# 05-STM32.net
KiCad netlist of a schematic drawn in Altium Designer
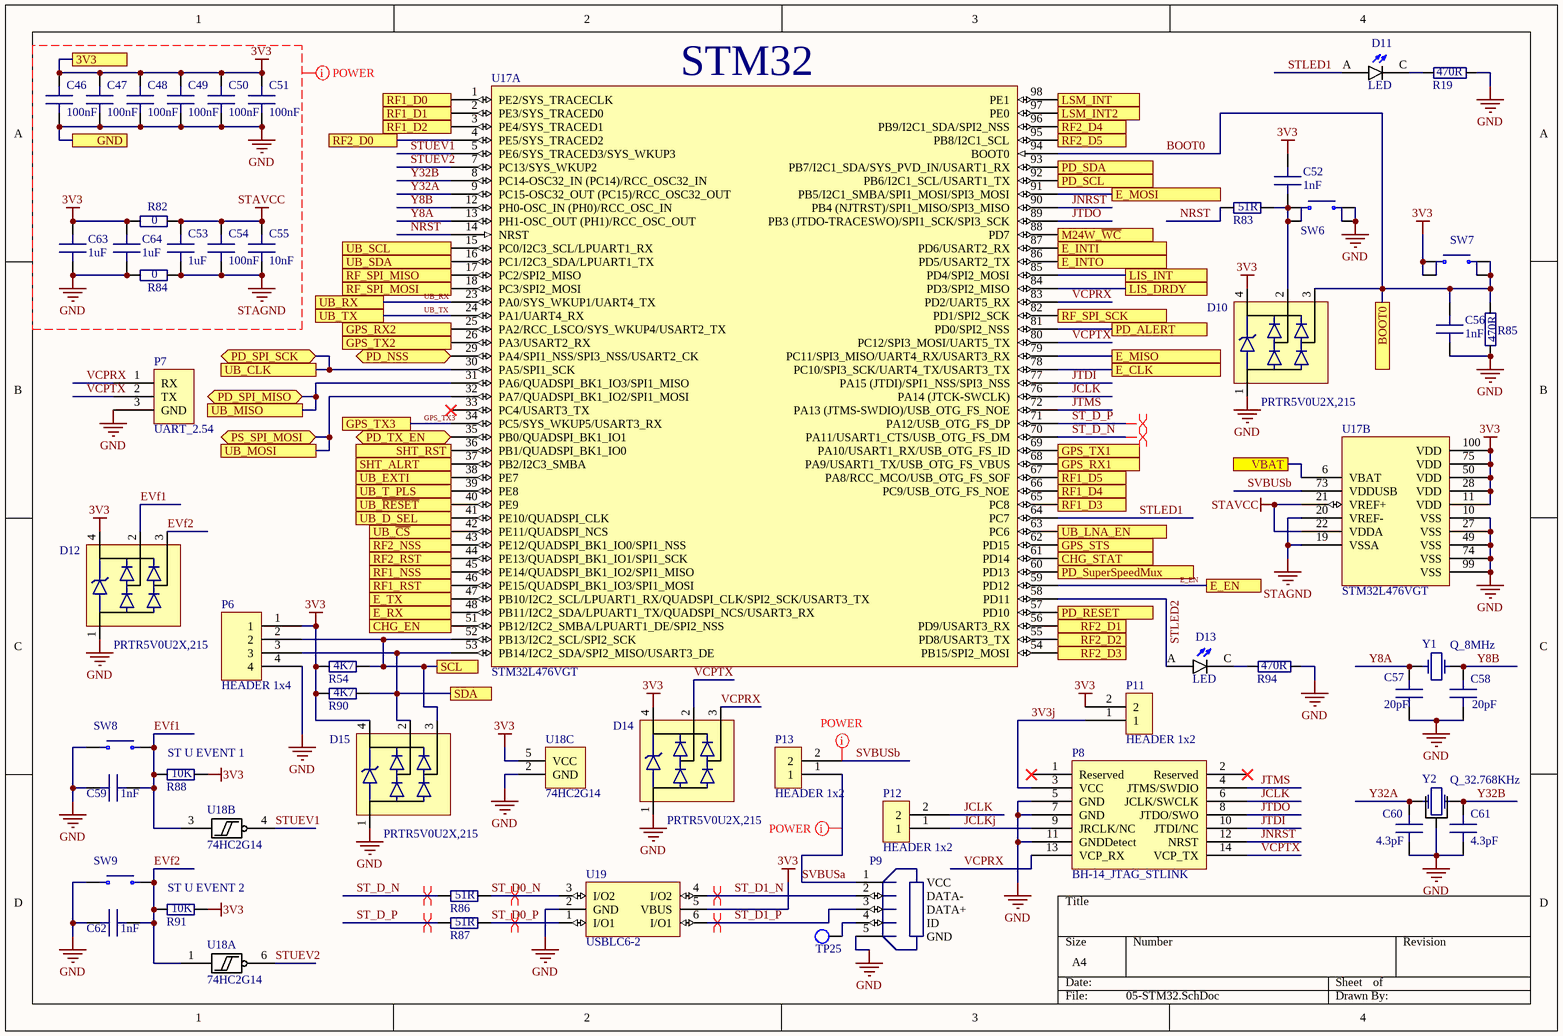
[diagram p0: 05-STM32.SchDoc]

(export (version "E")
  (design (tool "Eeschema 10.0.6"))
  (components
    (comp (ref "C46")
      (value "100nF")
      (footprint "C0603")
      (description "Ceramic capacitor")
      (fields (field (name "VOLTAGE") "16V"))
      (libsource (lib "A.Shelestov_Capacitors") (part "C0603_100nF_16V"))
    )
    (comp (ref "C47")
      (value "100nF")
      (footprint "C0603_NOSILK")
      (description "Ceramic capacitor")
      (fields (field (name "VOLTAGE") "16V"))
      (libsource (lib "A.Shelestov_Capacitors") (part "C0603_100nF_16V"))
    )
    (comp (ref "C48")
      (value "100nF")
      (footprint "C0603")
      (description "Ceramic capacitor")
      (fields (field (name "VOLTAGE") "16V"))
      (libsource (lib "A.Shelestov_Capacitors") (part "C0603_100nF_16V"))
    )
    (comp (ref "C49")
      (value "100nF")
      (footprint "C0603")
      (description "Ceramic capacitor")
      (fields (field (name "VOLTAGE") "16V"))
      (libsource (lib "A.Shelestov_Capacitors") (part "C0603_100nF_16V"))
    )
    (comp (ref "C50")
      (value "100nF")
      (footprint "C0603")
      (description "Ceramic capacitor")
      (fields (field (name "VOLTAGE") "16V"))
      (libsource (lib "A.Shelestov_Capacitors") (part "C0603_100nF_16V"))
    )
    (comp (ref "C51")
      (value "100nF")
      (footprint "C0603")
      (description "Ceramic capacitor")
      (fields (field (name "VOLTAGE") "16V"))
      (libsource (lib "A.Shelestov_Capacitors") (part "C0603_100nF_16V"))
    )
    (comp (ref "C52")
      (value "1nF")
      (footprint "C0603")
      (description "Ceramic capacitor")
      (fields (field (name "VOLTAGE") "25V"))
      (libsource (lib "A.Shelestov_Capacitors") (part "C0603_1nF_25V"))
    )
    (comp (ref "C53")
      (value "1uF")
      (footprint "C0805")
      (description "Ceramic capacitor")
      (fields (field (name "VOLTAGE") "25V"))
      (libsource (lib "A.Shelestov_Capacitors") (part "C0805_1uF_25V"))
    )
    (comp (ref "C54")
      (value "100nF")
      (footprint "C0603")
      (description "Ceramic capacitor")
      (fields (field (name "VOLTAGE") "16V"))
      (libsource (lib "A.Shelestov_Capacitors") (part "C0603_100nF_16V"))
    )
    (comp (ref "C55")
      (value "10nF")
      (footprint "C0603")
      (description "Ceramic capacitor")
      (fields (field (name "VOLTAGE") "16V"))
      (libsource (lib "A.Shelestov_Capacitors") (part "C0603_10nF_16V"))
    )
    (comp (ref "C56")
      (value "1nF")
      (footprint "C0603")
      (description "Ceramic capacitor")
      (fields (field (name "VOLTAGE") "25V"))
      (libsource (lib "A.Shelestov_Capacitors") (part "C0603_1nF_25V"))
    )
    (comp (ref "C57")
      (value "20pF")
      (footprint "C0603")
      (description "Ceramic capacitor")
      (fields (field (name "VOLTAGE") "25V"))
      (libsource (lib "A.Shelestov_Capacitors") (part "C0603_20pF_50V"))
    )
    (comp (ref "C58")
      (value "20pF")
      (footprint "C0603")
      (description "Ceramic capacitor")
      (fields (field (name "VOLTAGE") "25V"))
      (libsource (lib "A.Shelestov_Capacitors") (part "C0603_20pF_50V"))
    )
    (comp (ref "C59")
      (value "1nF")
      (footprint "C0603")
      (description "Ceramic capacitor")
      (fields (field (name "VOLTAGE") "25V"))
      (libsource (lib "A.Shelestov_Capacitors") (part "C0603_1nF_25V"))
    )
    (comp (ref "C60")
      (value "4.3pF")
      (footprint "C0603")
      (description "Ceramic capacitor")
      (fields (field (name "VOLTAGE") "25V"))
      (libsource (lib "A.Shelestov_Capacitors") (part "C0603_4.3pF_50V"))
    )
    (comp (ref "C61")
      (value "4.3pF")
      (footprint "C0603")
      (description "Ceramic capacitor")
      (fields (field (name "VOLTAGE") "25V"))
      (libsource (lib "A.Shelestov_Capacitors") (part "C0603_4.3pF_50V"))
    )
    (comp (ref "C62")
      (value "1nF")
      (footprint "C0603")
      (description "Ceramic capacitor")
      (fields (field (name "VOLTAGE") "25V"))
      (libsource (lib "A.Shelestov_Capacitors") (part "C0603_1nF_25V"))
    )
    (comp (ref "C63")
      (value "1uF")
      (footprint "C0805")
      (description "Ceramic capacitor")
      (fields (field (name "VOLTAGE") "25V"))
      (libsource (lib "A.Shelestov_Capacitors") (part "C0805_1uF_25V"))
    )
    (comp (ref "C64")
      (value "1uF")
      (footprint "C0805")
      (description "Ceramic capacitor")
      (fields (field (name "VOLTAGE") "25V"))
      (libsource (lib "A.Shelestov_Capacitors") (part "C0805_1uF_25V"))
    )
    (comp (ref "D10")
      (value "PRTR5V0U2X,215")
      (footprint "SOT143B")
      (description "PRTR5V0U2X - Ultra low capacitance double rail-to-rail ESD protection diode")
      (fields (field (name "MF") "Nexperia USA"))
      (libsource (lib "ComponentsLib") (part "PRTR5V0U2X,215"))
    )
    (comp (ref "D11")
      (value "LED")
      (footprint "LED_0604")
      (description "Led General")
      (fields (field (name "MF") "Dialight") (field (name "MP") "598-8140-107F"))
      (libsource (lib "ComponentsLib") (part "LED"))
    )
    (comp (ref "D12")
      (value "PRTR5V0U2X,215")
      (footprint "SOT143B")
      (description "PRTR5V0U2X - Ultra low capacitance double rail-to-rail ESD protection diode")
      (fields (field (name "MF") "Nexperia USA"))
      (libsource (lib "ComponentsLib") (part "PRTR5V0U2X,215"))
    )
    (comp (ref "D13")
      (value "LED")
      (footprint "LED_0604")
      (description "Led General")
      (fields (field (name "MF") "Dialight") (field (name "MP") "598-8140-107F"))
      (libsource (lib "ComponentsLib") (part "LED"))
    )
    (comp (ref "D14")
      (value "PRTR5V0U2X,215")
      (footprint "SOT143B")
      (description "PRTR5V0U2X - Ultra low capacitance double rail-to-rail ESD protection diode")
      (fields (field (name "MF") "Nexperia USA"))
      (libsource (lib "ComponentsLib") (part "PRTR5V0U2X,215"))
    )
    (comp (ref "D15")
      (value "PRTR5V0U2X,215")
      (footprint "SOT143B")
      (description "PRTR5V0U2X - Ultra low capacitance double rail-to-rail ESD protection diode")
      (fields (field (name "MF") "Nexperia USA"))
      (libsource (lib "ComponentsLib") (part "PRTR5V0U2X,215"))
    )
    (comp (ref "P6")
      (value "HEADER 1x4")
      (footprint "HEADER 1x4 2.54")
      (libsource (lib "ComponentsLib") (part "HEADER 1x4"))
    )
    (comp (ref "P7")
      (value "UART_2.54")
      (footprint "UART_2.54")
      (libsource (lib "ComponentsLib") (part "UART_2.54"))
    )
    (comp (ref "P8")
      (value "BH-14_JTAG_STLINK")
      (footprint "BH-14-1.27")
      (description "1,27 mm 2x7 Header")
      (libsource (lib "ComponentsLib") (part "BH-14_JTAG_STLINK"))
    )
    (comp (ref "P9")
      (value "440247-2")
      (footprint "CON-UUSB-F-2")
      (description "Mini/Micro USB B Type RCPT")
      (fields (field (name "MF") "TE Connectivity"))
      (libsource (lib "ComponentsLib") (part "CON-USB-Micro/Mini"))
    )
    (comp (ref "P11")
      (value "HEADER 1x2")
      (footprint "HEADER 1x2 2.54")
      (libsource (lib "ComponentsLib") (part "HEADER 1x2"))
    )
    (comp (ref "P12")
      (value "HEADER 1x2")
      (footprint "HEADER 1x2 2.54")
      (libsource (lib "") (part "HEADER 1x2_1"))
    )
    (comp (ref "P13")
      (value "HEADER 1x2")
      (footprint "HEADER 1x2 2.54")
      (libsource (lib "") (part "HEADER 1x2_1"))
    )
    (comp (ref "R19")
      (value "~")
      (footprint "R0603")
      (description "Resistor General")
      (fields (field (name "TOLERANCE") "5%") (field (name "RESISTANCE") "470R"))
      (libsource (lib "A.Shelestov_Resistors") (part "R0603_470R"))
    )
    (comp (ref "R54")
      (value "~")
      (footprint "R0603")
      (description "Resistor General")
      (fields (field (name "TOLERANCE") "5%") (field (name "RESISTANCE") "4K7"))
      (libsource (lib "A.Shelestov_Resistors") (part "R0603_4K7"))
    )
    (comp (ref "R82")
      (value "~")
      (footprint "R0603")
      (description "Resistor General")
      (fields (field (name "RESISTANCE") "0"))
      (libsource (lib "A.Shelestov_Resistors") (part "R0603_0R"))
    )
    (comp (ref "R83")
      (value "~")
      (footprint "R0402")
      (description "Resistor General")
      (fields (field (name "RESISTANCE") "51R"))
      (libsource (lib "A.Shelestov_Resistors") (part "R0402_51R"))
    )
    (comp (ref "R84")
      (value "~")
      (footprint "R0603")
      (description "Resistor General")
      (fields (field (name "RESISTANCE") "0"))
      (libsource (lib "A.Shelestov_Resistors") (part "R0603_0R"))
    )
    (comp (ref "R85")
      (value "~")
      (footprint "R0603")
      (description "Resistor General")
      (fields (field (name "TOLERANCE") "5%") (field (name "RESISTANCE") "470R"))
      (libsource (lib "A.Shelestov_Resistors") (part "R0603_470R"))
    )
    (comp (ref "R86")
      (value "~")
      (footprint "R0402")
      (description "Resistor General")
      (fields (field (name "RESISTANCE") "51R"))
      (libsource (lib "A.Shelestov_Resistors") (part "R0402_51R"))
    )
    (comp (ref "R87")
      (value "~")
      (footprint "R0402")
      (description "Resistor General")
      (fields (field (name "RESISTANCE") "51R"))
      (libsource (lib "A.Shelestov_Resistors") (part "R0402_51R"))
    )
    (comp (ref "R88")
      (value "~")
      (footprint "R0603")
      (description "Resistor General")
      (fields (field (name "TOLERANCE") "5%") (field (name "RESISTANCE") "10K"))
      (libsource (lib "A.Shelestov_Resistors") (part "R0603_10K"))
    )
    (comp (ref "R90")
      (value "~")
      (footprint "R0603")
      (description "Resistor General")
      (fields (field (name "TOLERANCE") "5%") (field (name "RESISTANCE") "4K7"))
      (libsource (lib "A.Shelestov_Resistors") (part "R0603_4K7"))
    )
    (comp (ref "R91")
      (value "~")
      (footprint "R0603")
      (description "Resistor General")
      (fields (field (name "TOLERANCE") "5%") (field (name "RESISTANCE") "10K"))
      (libsource (lib "A.Shelestov_Resistors") (part "R0603_10K"))
    )
    (comp (ref "R94")
      (value "~")
      (footprint "R0603")
      (description "Resistor General")
      (fields (field (name "TOLERANCE") "5%") (field (name "RESISTANCE") "470R"))
      (libsource (lib "A.Shelestov_Resistors") (part "R0603_470R"))
    )
    (comp (ref "SW6")
      (value "SWITCH_GEN_4P")
      (footprint "SW_4x4x1.5")
      (description "SWITCH DIP 4.3 mm")
      (libsource (lib "ComponentsLib") (part "SWITCH_GEN_4P"))
    )
    (comp (ref "SW7")
      (value "SWITCH_GEN_4P")
      (footprint "SW_4x4x1.5")
      (description "SWITCH DIP 4.3 mm")
      (libsource (lib "ComponentsLib") (part "SWITCH_GEN_4P"))
    )
    (comp (ref "SW8")
      (value "SWITCH_GEN_2P")
      (footprint "SW_TACTM-35N-F")
      (description "SWITCH DIP 4.3 mm")
      (libsource (lib "ComponentsLib") (part "SWITCH_GEN_2P"))
    )
    (comp (ref "SW9")
      (value "SWITCH_GEN_2P")
      (footprint "SW_TACTM-35N-F")
      (description "SWITCH DIP 4.3 mm")
      (libsource (lib "ComponentsLib") (part "SWITCH_GEN_2P"))
    )
    (comp (ref "TP25")
      (value "TEST_POINT")
      (footprint "TP_1mm")
      (libsource (lib "ComponentsLib") (part "TEST_POINT"))
    )
    (comp (ref "U17")
      (value "STM32L476VGT")
      (footprint "LQFP100_0.5")
      (description "Ultra-low-power Cortex-M4 32-bit MCU+FPU, 100DMIPS, up to 1MB Flash, 128 KB SRAM, USB OTG FS, LCD")
      (libsource (lib "ComponentsLib") (part "STM32L476VGT"))
    )
    (comp (ref "U18")
      (value "74HC2G14")
      (footprint "SOT363/SOT65P210X110-6N")
      (description "Dual inverting Schmitt trigger")
      (libsource (lib "ComponentsLib") (part "74HC2G14"))
    )
    (comp (ref "U19")
      (value "USBLC6-2")
      (footprint "SOT-666")
      (description "Very low capacitance ESD protection")
      (libsource (lib "ComponentsLib") (part "USBLC6-2"))
    )
    (comp (ref "Y1")
      (value "Q_8MHz")
      (footprint "QSMD12.3x4.5x4.2")
      (description "Quartz resonator 8MHz")
      (libsource (lib "ComponentsLib") (part "Q_8MHz"))
    )
    (comp (ref "Y2")
      (value "Q_32.768KHz")
      (footprint "HC_3.0x8.0")
      (description "Quartz resonator 32.768KHz")
      (libsource (lib "ComponentsLib") (part "Q_32.768KHz"))
    )
  )
  (nets
    (net (code "1") (name "/3V3j") (class "Default")
      (node (ref "P11") (pin "1") (pinfunction "1_1") (pintype "passive"))
      (node (ref "P8") (pin "3") (pinfunction "VCC_3") (pintype "passive"))
    )
    (net (code "2") (name "/BOOT0") (class "Default")
      (node (ref "C56") (pin "1") (pinfunction "1_1") (pintype "passive"))
      (node (ref "D10") (pin "3") (pinfunction "P$3_3") (pintype "passive"))
      (node (ref "R85") (pin "2") (pinfunction "2_2") (pintype "passive"))
      (node (ref "SW7") (pin "1") (pinfunction "1_1") (pintype "passive"))
      (node (ref "SW7") (pin "3") (pinfunction "3_3") (pintype "passive"))
      (node (ref "U17") (pin "94") (pinfunction "BOOT0_94") (pintype "input"))
    )
    (net (code "3") (name "/CHG_EN") (class "Default")
      (node (ref "U17") (pin "51") (pinfunction "PB12/I2C2_SMBA/LPUART1_DE/SPI2_NSS_51") (pintype "bidirectional"))
    )
    (net (code "4") (name "/CHG_STAT") (class "Default")
      (node (ref "U17") (pin "61") (pinfunction "PD14_61") (pintype "bidirectional"))
    )
    (net (code "5") (name "/EVf1") (class "Default")
      (node (ref "C59") (pin "1") (pinfunction "1_1") (pintype "passive"))
      (node (ref "D12") (pin "2") (pinfunction "P$2_2") (pintype "passive"))
      (node (ref "R88") (pin "1") (pinfunction "1_1") (pintype "passive"))
      (node (ref "SW8") (pin "2") (pinfunction "2_2") (pintype "passive"))
      (node (ref "U18") (pin "3") (pinfunction "2A_3") (pintype "passive"))
    )
    (net (code "6") (name "/EVf2") (class "Default")
      (node (ref "C62") (pin "1") (pinfunction "1_1") (pintype "passive"))
      (node (ref "D12") (pin "3") (pinfunction "P$3_3") (pintype "passive"))
      (node (ref "R91") (pin "1") (pinfunction "1_1") (pintype "passive"))
      (node (ref "SW9") (pin "2") (pinfunction "2_2") (pintype "passive"))
      (node (ref "U18") (pin "1") (pinfunction "1A_1") (pintype "passive"))
    )
    (net (code "7") (name "/E_CLK") (class "Default")
      (node (ref "U17") (pin "78") (pinfunction "PC10/SPI3_SCK/UART4_TX/USART3_TX_78") (pintype "bidirectional"))
    )
    (net (code "8") (name "/E_EN") (class "Default")
      (node (ref "U17") (pin "59") (pinfunction "PD12_59") (pintype "bidirectional"))
    )
    (net (code "9") (name "/E_INTI") (class "Default")
      (node (ref "U17") (pin "87") (pinfunction "PD6/USART2_RX_87") (pintype "bidirectional"))
    )
    (net (code "10") (name "/E_INTO") (class "Default")
      (node (ref "U17") (pin "86") (pinfunction "PD5/USART2_TX_86") (pintype "bidirectional"))
    )
    (net (code "11") (name "/E_MISO") (class "Default")
      (node (ref "U17") (pin "79") (pinfunction "PC11/SPI3_MISO/UART4_RX/USART3_RX_79") (pintype "bidirectional"))
    )
    (net (code "12") (name "/E_MOSI") (class "Default")
      (node (ref "U17") (pin "91") (pinfunction "PB5/I2C1_SMBA/SPI1_MOSI/SPI3_MOSI_91") (pintype "bidirectional"))
    )
    (net (code "13") (name "/E_RX") (class "Default")
      (node (ref "U17") (pin "48") (pinfunction "PB11/I2C2_SDA/LPUART1_TX/QUADSPI_NCS/USART3_RX_48") (pintype "bidirectional"))
    )
    (net (code "14") (name "/E_TX") (class "Default")
      (node (ref "U17") (pin "47") (pinfunction "PB10/I2C2_SCL/LPUART1_RX/QUADSPI_CLK/SPI2_SCK/USART3_TX_47") (pintype "bidirectional"))
    )
    (net (code "15") (name "/GPS_RX1") (class "Default")
      (node (ref "U17") (pin "68") (pinfunction "PA9/USART1_TX/USB_OTG_FS_VBUS_68") (pintype "bidirectional"))
    )
    (net (code "16") (name "/GPS_RX2") (class "Default")
      (node (ref "U17") (pin "25") (pinfunction "PA2/RCC_LSCO/SYS_WKUP4/USART2_TX_25") (pintype "bidirectional"))
    )
    (net (code "17") (name "/GPS_STS") (class "Default")
      (node (ref "U17") (pin "62") (pinfunction "PD15_62") (pintype "bidirectional"))
    )
    (net (code "18") (name "/GPS_TX1") (class "Default")
      (node (ref "U17") (pin "69") (pinfunction "PA10/USART1_RX/USB_OTG_FS_ID_69") (pintype "bidirectional"))
    )
    (net (code "19") (name "/GPS_TX2") (class "Default")
      (node (ref "U17") (pin "26") (pinfunction "PA3/USART2_RX_26") (pintype "bidirectional"))
    )
    (net (code "20") (name "/GPS_TX3") (class "Default")
      (node (ref "U17") (pin "34") (pinfunction "PC5/SYS_WKUP5/USART3_RX_34") (pintype "bidirectional"))
    )
    (net (code "21") (name "/JCLK") (class "Default")
      (node (ref "P12") (pin "2") (pinfunction "2_2") (pintype "passive"))
      (node (ref "P8") (pin "6") (pinfunction "JCLK/SWCLK_6") (pintype "passive"))
      (node (ref "U17") (pin "76") (pinfunction "PA14_(JTCK-SWCLK)_76") (pintype "bidirectional"))
    )
    (net (code "22") (name "/JCLKj") (class "Default")
      (node (ref "P12") (pin "1") (pinfunction "1_1") (pintype "passive"))
      (node (ref "P8") (pin "9") (pinfunction "JRCLK/NC_9") (pintype "passive"))
    )
    (net (code "23") (name "/JNRST") (class "Default")
      (node (ref "P8") (pin "12") (pinfunction "NRST_12") (pintype "passive"))
      (node (ref "U17") (pin "90") (pinfunction "PB4_(NJTRST)/SPI1_MISO/SPI3_MISO_90") (pintype "bidirectional"))
    )
    (net (code "24") (name "/JTDI") (class "Default")
      (node (ref "P8") (pin "10") (pinfunction "JTDI/NC_10") (pintype "passive"))
      (node (ref "U17") (pin "77") (pinfunction "PA15_(JTDI)/SPI1_NSS/SPI3_NSS_77") (pintype "bidirectional"))
    )
    (net (code "25") (name "/JTDO") (class "Default")
      (node (ref "P8") (pin "8") (pinfunction "JTDO/SWO_8") (pintype "passive"))
      (node (ref "U17") (pin "89") (pinfunction "PB3_(JTDO-TRACESWO)/SPI1_SCK/SPI3_SCK_89") (pintype "bidirectional"))
    )
    (net (code "26") (name "/JTMS") (class "Default")
      (node (ref "P8") (pin "4") (pinfunction "JTMS/SWDIO_4") (pintype "passive"))
      (node (ref "U17") (pin "72") (pinfunction "PA13_(JTMS-SWDIO)/USB_OTG_FS_NOE_72") (pintype "bidirectional"))
    )
    (net (code "27") (name "/LIS_DRDY") (class "Default")
      (node (ref "U17") (pin "84") (pinfunction "PD3/SPI2_MISO_84") (pintype "bidirectional"))
    )
    (net (code "28") (name "/LIS_INT") (class "Default")
      (node (ref "U17") (pin "85") (pinfunction "PD4/SPI2_MOSI_85") (pintype "bidirectional"))
    )
    (net (code "29") (name "/LSM_INT") (class "Default")
      (node (ref "U17") (pin "98") (pinfunction "PE1_98") (pintype "bidirectional"))
    )
    (net (code "30") (name "/LSM_INT2") (class "Default")
      (node (ref "U17") (pin "97") (pinfunction "PE0_97") (pintype "bidirectional"))
    )
    (net (code "31") (name "/M24W_~{WC}") (class "Default")
      (node (ref "U17") (pin "88") (pinfunction "PD7_88") (pintype "bidirectional"))
    )
    (net (code "32") (name "/NRST") (class "Default")
      (node (ref "R83") (pin "1") (pinfunction "1_1") (pintype "passive"))
      (node (ref "U17") (pin "14") (pinfunction "NRST_14") (pintype "input"))
    )
    (net (code "33") (name "/PD_ALERT") (class "Default")
      (node (ref "U17") (pin "81") (pinfunction "PD0/SPI2_NSS_81") (pintype "bidirectional"))
    )
    (net (code "34") (name "/PD_NSS") (class "Default")
      (node (ref "U17") (pin "29") (pinfunction "PA4/SPI1_NSS/SPI3_NSS/USART2_CK_29") (pintype "bidirectional"))
    )
    (net (code "35") (name "/PD_RESET") (class "Default")
      (node (ref "U17") (pin "57") (pinfunction "PD10_57") (pintype "bidirectional"))
    )
    (net (code "36") (name "/PD_SCL") (class "Default")
      (node (ref "U17") (pin "92") (pinfunction "PB6/I2C1_SCL/USART1_TX_92") (pintype "bidirectional"))
    )
    (net (code "37") (name "/PD_SDA") (class "Default")
      (node (ref "U17") (pin "93") (pinfunction "PB7/I2C1_SDA/SYS_PVD_IN/USART1_RX_93") (pintype "bidirectional"))
    )
    (net (code "38") (name "/PD_SPI_MISO") (class "Default")
      (node (ref "U17") (pin "31") (pinfunction "PA6/QUADSPI_BK1_IO3/SPI1_MISO_31") (pintype "bidirectional"))
    )
    (net (code "39") (name "/PD_SPI_SCK") (class "Default")
      (node (ref "U17") (pin "30") (pinfunction "PA5/SPI1_SCK_30") (pintype "bidirectional"))
    )
    (net (code "40") (name "/PD_SuperSpeedMux") (class "Default")
      (node (ref "U17") (pin "60") (pinfunction "PD13_60") (pintype "bidirectional"))
    )
    (net (code "41") (name "/PD_TX_EN") (class "Default")
      (node (ref "U17") (pin "35") (pinfunction "PB0/QUADSPI_BK1_IO1_35") (pintype "bidirectional"))
    )
    (net (code "42") (name "/PS_SPI_MOSI") (class "Default")
      (node (ref "U17") (pin "32") (pinfunction "PA7/QUADSPI_BK1_IO2/SPI1_MOSI_32") (pintype "bidirectional"))
    )
    (net (code "43") (name "/RF1_D0") (class "Default")
      (node (ref "U17") (pin "1") (pinfunction "PE2/SYS_TRACECLK_1") (pintype "bidirectional"))
    )
    (net (code "44") (name "/RF1_D1") (class "Default")
      (node (ref "U17") (pin "2") (pinfunction "PE3/SYS_TRACED0_2") (pintype "bidirectional"))
    )
    (net (code "45") (name "/RF1_D2") (class "Default")
      (node (ref "U17") (pin "3") (pinfunction "PE4/SYS_TRACED1_3") (pintype "bidirectional"))
    )
    (net (code "46") (name "/RF1_D3") (class "Default")
      (node (ref "U17") (pin "65") (pinfunction "PC8_65") (pintype "bidirectional"))
    )
    (net (code "47") (name "/RF1_D4") (class "Default")
      (node (ref "U17") (pin "66") (pinfunction "PC9/USB_OTG_FS_NOE_66") (pintype "bidirectional"))
    )
    (net (code "48") (name "/RF1_D5") (class "Default")
      (node (ref "U17") (pin "67") (pinfunction "PA8/RCC_MCO/USB_OTG_FS_SOF_67") (pintype "bidirectional"))
    )
    (net (code "49") (name "/RF1_NSS") (class "Default")
      (node (ref "U17") (pin "45") (pinfunction "PE14/QUADSPI_BK1_IO2/SPI1_MISO_45") (pintype "bidirectional"))
    )
    (net (code "50") (name "/RF1_RST") (class "Default")
      (node (ref "U17") (pin "46") (pinfunction "PE15/QUADSPI_BK1_IO3/SPI1_MOSI_46") (pintype "bidirectional"))
    )
    (net (code "51") (name "/RF2_D0") (class "Default")
      (node (ref "U17") (pin "4") (pinfunction "PE5/SYS_TRACED2_4") (pintype "bidirectional"))
    )
    (net (code "52") (name "/RF2_D1") (class "Default")
      (node (ref "U17") (pin "56") (pinfunction "PD9/USART3_RX_56") (pintype "bidirectional"))
    )
    (net (code "53") (name "/RF2_D2") (class "Default")
      (node (ref "U17") (pin "55") (pinfunction "PD8/USART3_TX_55") (pintype "bidirectional"))
    )
    (net (code "54") (name "/RF2_D3") (class "Default")
      (node (ref "U17") (pin "54") (pinfunction "PB15/SPI2_MOSI_54") (pintype "bidirectional"))
    )
    (net (code "55") (name "/RF2_D4") (class "Default")
      (node (ref "U17") (pin "96") (pinfunction "PB9/I2C1_SDA/SPI2_NSS_96") (pintype "bidirectional"))
    )
    (net (code "56") (name "/RF2_D5") (class "Default")
      (node (ref "U17") (pin "95") (pinfunction "PB8/I2C1_SCL_95") (pintype "bidirectional"))
    )
    (net (code "57") (name "/RF2_NSS") (class "Default")
      (node (ref "U17") (pin "43") (pinfunction "PE12/QUADSPI_BK1_IO0/SPI1_NSS_43") (pintype "bidirectional"))
    )
    (net (code "58") (name "/RF2_RST") (class "Default")
      (node (ref "U17") (pin "44") (pinfunction "PE13/QUADSPI_BK1_IO1/SPI1_SCK_44") (pintype "bidirectional"))
    )
    (net (code "59") (name "/RF_SPI_MISO") (class "Default")
      (node (ref "U17") (pin "17") (pinfunction "PC2/SPI2_MISO_17") (pintype "bidirectional"))
    )
    (net (code "60") (name "/RF_SPI_MOSI") (class "Default")
      (node (ref "U17") (pin "18") (pinfunction "PC3/SPI2_MOSI_18") (pintype "bidirectional"))
    )
    (net (code "61") (name "/RF_SPI_SCK") (class "Default")
      (node (ref "U17") (pin "82") (pinfunction "PD1/SPI2_SCK_82") (pintype "bidirectional"))
    )
    (net (code "62") (name "/SCL") (class "Default")
      (node (ref "D15") (pin "3") (pinfunction "P$3_3") (pintype "passive"))
      (node (ref "P6") (pin "2") (pinfunction "2_2") (pintype "passive"))
      (node (ref "R54") (pin "2") (pinfunction "2_2") (pintype "passive"))
      (node (ref "U17") (pin "52") (pinfunction "PB13/I2C2_SCL/SPI2_SCK_52") (pintype "bidirectional"))
    )
    (net (code "63") (name "/SDA") (class "Default")
      (node (ref "D15") (pin "2") (pinfunction "P$2_2") (pintype "passive"))
      (node (ref "P6") (pin "3") (pinfunction "3_3") (pintype "passive"))
      (node (ref "R90") (pin "2") (pinfunction "2_2") (pintype "passive"))
      (node (ref "U17") (pin "53") (pinfunction "PB14/I2C2_SDA/SPI2_MISO/USART3_DE_53") (pintype "bidirectional"))
    )
    (net (code "64") (name "/SHT_ALRT") (class "Default")
      (node (ref "U17") (pin "37") (pinfunction "PB2/I2C3_SMBA_37") (pintype "bidirectional"))
    )
    (net (code "65") (name "/SHT_RST") (class "Default")
      (node (ref "U17") (pin "36") (pinfunction "PB1/QUADSPI_BK1_IO0_36") (pintype "bidirectional"))
    )
    (net (code "66") (name "/STLED1") (class "Default")
      (node (ref "D11") (pin "A") (pinfunction "A_A") (pintype "passive"))
      (node (ref "U17") (pin "64") (pinfunction "PC7_64") (pintype "bidirectional"))
    )
    (net (code "67") (name "/STLED2") (class "Default")
      (node (ref "D13") (pin "A") (pinfunction "A_A") (pintype "passive"))
      (node (ref "U17") (pin "58") (pinfunction "PD11_58") (pintype "bidirectional"))
    )
    (net (code "68") (name "/STUEV1") (class "Default")
      (node (ref "U17") (pin "5") (pinfunction "PE6/SYS_TRACED3/SYS_WKUP3_5") (pintype "bidirectional"))
      (node (ref "U18") (pin "4") (pinfunction "2Y_4") (pintype "passive"))
    )
    (net (code "69") (name "/STUEV2") (class "Default")
      (node (ref "U17") (pin "7") (pinfunction "PC13/SYS_WKUP2_7") (pintype "bidirectional"))
      (node (ref "U18") (pin "6") (pinfunction "1Y_6") (pintype "passive"))
    )
    (net (code "70") (name "/ST_D0_N") (class "Default")
      (node (ref "R86") (pin "2") (pinfunction "2_2") (pintype "passive"))
      (node (ref "U19") (pin "3") (pinfunction "I/O2_3") (pintype "bidirectional"))
    )
    (net (code "71") (name "/ST_D0_P") (class "Default")
      (node (ref "R87") (pin "2") (pinfunction "2_2") (pintype "passive"))
      (node (ref "U19") (pin "1") (pinfunction "I/O1_1") (pintype "bidirectional"))
    )
    (net (code "72") (name "/ST_D1_N") (class "Default")
      (node (ref "P9") (pin "2") (pinfunction "DATA-_2") (pintype "bidirectional"))
      (node (ref "U19") (pin "4") (pinfunction "I/O2_4") (pintype "bidirectional"))
    )
    (net (code "73") (name "/ST_D1_P") (class "Default")
      (node (ref "P9") (pin "3") (pinfunction "DATA+_3") (pintype "bidirectional"))
      (node (ref "U19") (pin "6") (pinfunction "I/O1_6") (pintype "bidirectional"))
    )
    (net (code "74") (name "/ST_D_N") (class "Default")
      (node (ref "R86") (pin "1") (pinfunction "1_1") (pintype "passive"))
      (node (ref "U17") (pin "70") (pinfunction "PA11/USART1_CTS/USB_OTG_FS_DM_70") (pintype "bidirectional"))
    )
    (net (code "75") (name "/ST_D_P") (class "Default")
      (node (ref "R87") (pin "1") (pinfunction "1_1") (pintype "passive"))
      (node (ref "U17") (pin "71") (pinfunction "PA12/USB_OTG_FS_DP_71") (pintype "bidirectional"))
    )
    (net (code "76") (name "/SVBUSa") (class "Default")
      (node (ref "P13") (pin "1") (pinfunction "1_1") (pintype "passive"))
      (node (ref "P9") (pin "1") (pinfunction "VCC_1") (pintype "power_in"))
    )
    (net (code "77") (name "/SVBUSb") (class "Default")
      (node (ref "P13") (pin "2") (pinfunction "2_2") (pintype "passive"))
      (node (ref "U17") (pin "73") (pinfunction "VDDUSB_73") (pintype "power_in"))
    )
    (net (code "78") (name "/UB_D_SEL") (class "Default")
      (node (ref "U17") (pin "41") (pinfunction "PE10/QUADSPI_CLK_41") (pintype "bidirectional"))
    )
    (net (code "79") (name "/UB_EXTI") (class "Default")
      (node (ref "U17") (pin "38") (pinfunction "PE7_38") (pintype "bidirectional"))
    )
    (net (code "80") (name "/UB_LNA_EN") (class "Default")
      (node (ref "U17") (pin "63") (pinfunction "PC6_63") (pintype "bidirectional"))
    )
    (net (code "81") (name "/UB_RX") (class "Default")
      (node (ref "U17") (pin "23") (pinfunction "PA0/SYS_WKUP1/UART4_TX_23") (pintype "bidirectional"))
    )
    (net (code "82") (name "/UB_SCL") (class "Default")
      (node (ref "U17") (pin "15") (pinfunction "PC0/I2C3_SCL/LPUART1_RX_15") (pintype "bidirectional"))
    )
    (net (code "83") (name "/UB_SDA") (class "Default")
      (node (ref "U17") (pin "16") (pinfunction "PC1/I2C3_SDA/LPUART1_TX_16") (pintype "bidirectional"))
    )
    (net (code "84") (name "/UB_TX") (class "Default")
      (node (ref "U17") (pin "24") (pinfunction "PA1/UART4_RX_24") (pintype "bidirectional"))
    )
    (net (code "85") (name "/UB_T_PLS") (class "Default")
      (node (ref "U17") (pin "39") (pinfunction "PE8_39") (pintype "bidirectional"))
    )
    (net (code "86") (name "/UB_~{CS}") (class "Default")
      (node (ref "U17") (pin "42") (pinfunction "PE11/QUADSPI_NCS_42") (pintype "bidirectional"))
    )
    (net (code "87") (name "/UB_~{RESET}") (class "Default")
      (node (ref "U17") (pin "40") (pinfunction "PE9_40") (pintype "bidirectional"))
    )
    (net (code "88") (name "/VBAT") (class "Default")
      (node (ref "U17") (pin "6") (pinfunction "VBAT_6") (pintype "power_in"))
    )
    (net (code "89") (name "/VCPRX") (class "Default")
      (node (ref "D14") (pin "3") (pinfunction "P$3_3") (pintype "passive"))
      (node (ref "P7") (pin "1") (pinfunction "RX_1") (pintype "passive"))
      (node (ref "P8") (pin "13") (pinfunction "VCP_RX_13") (pintype "passive"))
      (node (ref "U17") (pin "83") (pinfunction "PD2/UART5_RX_83") (pintype "bidirectional"))
    )
    (net (code "90") (name "/VCPTX") (class "Default")
      (node (ref "D14") (pin "2") (pinfunction "P$2_2") (pintype "passive"))
      (node (ref "P7") (pin "2") (pinfunction "TX_2") (pintype "passive"))
      (node (ref "P8") (pin "14") (pinfunction "VCP_TX_14") (pintype "passive"))
      (node (ref "U17") (pin "80") (pinfunction "PC12/SPI3_MOSI/UART5_TX_80") (pintype "bidirectional"))
    )
    (net (code "91") (name "/Y8A") (class "Default")
      (node (ref "C57") (pin "2") (pinfunction "2_2") (pintype "passive"))
      (node (ref "U17") (pin "13") (pinfunction "PH1-OSC_OUT_(PH1)/RCC_OSC_OUT_13") (pintype "bidirectional"))
      (node (ref "Y1") (pin "1") (pinfunction "1_1") (pintype "passive"))
    )
    (net (code "92") (name "/Y8B") (class "Default")
      (node (ref "C58") (pin "2") (pinfunction "2_2") (pintype "passive"))
      (node (ref "U17") (pin "12") (pinfunction "PH0-OSC_IN_(PH0)/RCC_OSC_IN_12") (pintype "bidirectional"))
      (node (ref "Y1") (pin "2") (pinfunction "2_2") (pintype "passive"))
    )
    (net (code "93") (name "/Y32A") (class "Default")
      (node (ref "C60") (pin "2") (pinfunction "2_2") (pintype "passive"))
      (node (ref "U17") (pin "9") (pinfunction "PC15-OSC32_OUT_(PC15)/RCC_OSC32_OUT_9") (pintype "bidirectional"))
      (node (ref "Y2") (pin "1") (pinfunction "1_1") (pintype "passive"))
    )
    (net (code "94") (name "/Y32B") (class "Default")
      (node (ref "C61") (pin "2") (pinfunction "2_2") (pintype "passive"))
      (node (ref "U17") (pin "8") (pinfunction "PC14-OSC32_IN_(PC14)/RCC_OSC32_IN_8") (pintype "bidirectional"))
      (node (ref "Y2") (pin "2") (pinfunction "2_2") (pintype "passive"))
    )
    (net (code "95") (name "3V3") (class "Default")
      (node (ref "C46") (pin "2") (pinfunction "2_2") (pintype "passive"))
      (node (ref "C47") (pin "2") (pinfunction "2_2") (pintype "passive"))
      (node (ref "C48") (pin "2") (pinfunction "2_2") (pintype "passive"))
      (node (ref "C49") (pin "2") (pinfunction "2_2") (pintype "passive"))
      (node (ref "C50") (pin "2") (pinfunction "2_2") (pintype "passive"))
      (node (ref "C51") (pin "2") (pinfunction "2_2") (pintype "passive"))
      (node (ref "C52") (pin "1") (pinfunction "1_1") (pintype "passive"))
      (node (ref "C63") (pin "2") (pinfunction "2_2") (pintype "passive"))
      (node (ref "C64") (pin "2") (pinfunction "2_2") (pintype "passive"))
      (node (ref "D10") (pin "4") (pinfunction "P$4_4") (pintype "passive"))
      (node (ref "D12") (pin "4") (pinfunction "P$4_4") (pintype "passive"))
      (node (ref "D14") (pin "4") (pinfunction "P$4_4") (pintype "passive"))
      (node (ref "D15") (pin "4") (pinfunction "P$4_4") (pintype "passive"))
      (node (ref "P11") (pin "2") (pinfunction "2_2") (pintype "passive"))
      (node (ref "P6") (pin "1") (pinfunction "1_1") (pintype "passive"))
      (node (ref "R54") (pin "1") (pinfunction "1_1") (pintype "passive"))
      (node (ref "R82") (pin "1") (pinfunction "1_1") (pintype "passive"))
      (node (ref "R88") (pin "2") (pinfunction "2_2") (pintype "passive"))
      (node (ref "R90") (pin "1") (pinfunction "1_1") (pintype "passive"))
      (node (ref "R91") (pin "2") (pinfunction "2_2") (pintype "passive"))
      (node (ref "SW7") (pin "2") (pinfunction "2_2") (pintype "passive"))
      (node (ref "SW7") (pin "4") (pinfunction "4_4") (pintype "passive"))
      (node (ref "U17") (pin "100") (pinfunction "VDD_100") (pintype "power_in"))
      (node (ref "U17") (pin "11") (pinfunction "VDD_11") (pintype "power_in"))
      (node (ref "U17") (pin "28") (pinfunction "VDD_28") (pintype "power_in"))
      (node (ref "U17") (pin "50") (pinfunction "VDD_50") (pintype "power_in"))
      (node (ref "U17") (pin "75") (pinfunction "VDD_75") (pintype "power_in"))
      (node (ref "U18") (pin "5") (pinfunction "VCC_5") (pintype "passive"))
      (node (ref "U19") (pin "5") (pinfunction "VBUS_5") (pintype "power_in"))
    )
    (net (code "96") (name "GND") (class "Default")
      (node (ref "C46") (pin "1") (pinfunction "1_1") (pintype "passive"))
      (node (ref "C47") (pin "1") (pinfunction "1_1") (pintype "passive"))
      (node (ref "C48") (pin "1") (pinfunction "1_1") (pintype "passive"))
      (node (ref "C49") (pin "1") (pinfunction "1_1") (pintype "passive"))
      (node (ref "C50") (pin "1") (pinfunction "1_1") (pintype "passive"))
      (node (ref "C51") (pin "1") (pinfunction "1_1") (pintype "passive"))
      (node (ref "C56") (pin "2") (pinfunction "2_2") (pintype "passive"))
      (node (ref "C57") (pin "1") (pinfunction "1_1") (pintype "passive"))
      (node (ref "C58") (pin "1") (pinfunction "1_1") (pintype "passive"))
      (node (ref "C59") (pin "2") (pinfunction "2_2") (pintype "passive"))
      (node (ref "C60") (pin "1") (pinfunction "1_1") (pintype "passive"))
      (node (ref "C61") (pin "1") (pinfunction "1_1") (pintype "passive"))
      (node (ref "C62") (pin "2") (pinfunction "2_2") (pintype "passive"))
      (node (ref "C63") (pin "1") (pinfunction "1_1") (pintype "passive"))
      (node (ref "C64") (pin "1") (pinfunction "1_1") (pintype "passive"))
      (node (ref "D10") (pin "1") (pinfunction "P$1_1") (pintype "passive"))
      (node (ref "D12") (pin "1") (pinfunction "P$1_1") (pintype "passive"))
      (node (ref "D14") (pin "1") (pinfunction "P$1_1") (pintype "passive"))
      (node (ref "D15") (pin "1") (pinfunction "P$1_1") (pintype "passive"))
      (node (ref "P6") (pin "4") (pinfunction "4_4") (pintype "passive"))
      (node (ref "P7") (pin "3") (pinfunction "GND_3") (pintype "passive"))
      (node (ref "P8") (pin "11") (pinfunction "GNDDetect_11") (pintype "passive"))
      (node (ref "P8") (pin "5") (pinfunction "GND_5") (pintype "passive"))
      (node (ref "P8") (pin "7") (pinfunction "GND_7") (pintype "passive"))
      (node (ref "P9") (pin "5") (pinfunction "GND_5") (pintype "passive"))
      (node (ref "R19") (pin "2") (pinfunction "2_2") (pintype "passive"))
      (node (ref "R84") (pin "1") (pinfunction "1_1") (pintype "passive"))
      (node (ref "R85") (pin "1") (pinfunction "1_1") (pintype "passive"))
      (node (ref "R94") (pin "2") (pinfunction "2_2") (pintype "passive"))
      (node (ref "SW6") (pin "1") (pinfunction "1_1") (pintype "passive"))
      (node (ref "SW6") (pin "3") (pinfunction "3_3") (pintype "passive"))
      (node (ref "SW8") (pin "1") (pinfunction "1_1") (pintype "passive"))
      (node (ref "SW9") (pin "1") (pinfunction "1_1") (pintype "passive"))
      (node (ref "U17") (pin "10") (pinfunction "VSS_10") (pintype "power_in"))
      (node (ref "U17") (pin "27") (pinfunction "VSS_27") (pintype "power_in"))
      (node (ref "U17") (pin "49") (pinfunction "VSS_49") (pintype "power_in"))
      (node (ref "U17") (pin "74") (pinfunction "VSS_74") (pintype "power_in"))
      (node (ref "U17") (pin "99") (pinfunction "VSS_99") (pintype "power_in"))
      (node (ref "U18") (pin "2") (pinfunction "GND_2") (pintype "passive"))
      (node (ref "U19") (pin "2") (pinfunction "GND_2") (pintype "power_in"))
      (node (ref "Y2") (pin "PAD") (pinfunction "PAD_PAD") (pintype "passive"))
    )
    (net (code "97") (name "Net-(D10-P$2)") (class "Default")
      (node (ref "C52") (pin "2") (pinfunction "2_2") (pintype "passive"))
      (node (ref "D10") (pin "2") (pinfunction "P$2_2") (pintype "passive"))
      (node (ref "R83") (pin "2") (pinfunction "2_2") (pintype "passive"))
      (node (ref "SW6") (pin "2") (pinfunction "2_2") (pintype "passive"))
      (node (ref "SW6") (pin "4") (pinfunction "4_4") (pintype "passive"))
    )
    (net (code "98") (name "Net-(D11-PadC)") (class "Default")
      (node (ref "D11") (pin "C") (pinfunction "C_C") (pintype "passive"))
      (node (ref "R19") (pin "1") (pinfunction "1_1") (pintype "passive"))
    )
    (net (code "99") (name "Net-(D13-PadC)") (class "Default")
      (node (ref "D13") (pin "C") (pinfunction "C_C") (pintype "passive"))
      (node (ref "R94") (pin "1") (pinfunction "1_1") (pintype "passive"))
    )
    (net (code "100") (name "Net-(P9-ID)") (class "Default")
      (node (ref "P9") (pin "4") (pinfunction "ID_4") (pintype "bidirectional"))
      (node (ref "TP25") (pin "1") (pinfunction "1_1") (pintype "passive"))
    )
    (net (code "101") (name "STAGND") (class "Default")
      (node (ref "C53") (pin "1") (pinfunction "1_1") (pintype "passive"))
      (node (ref "C54") (pin "1") (pinfunction "1_1") (pintype "passive"))
      (node (ref "C55") (pin "1") (pinfunction "1_1") (pintype "passive"))
      (node (ref "R84") (pin "2") (pinfunction "2_2") (pintype "passive"))
      (node (ref "U17") (pin "19") (pinfunction "VSSA_19") (pintype "power_in"))
      (node (ref "U17") (pin "20") (pinfunction "VREF-_20") (pintype "power_in"))
    )
    (net (code "102") (name "STAVCC") (class "Default")
      (node (ref "C53") (pin "2") (pinfunction "2_2") (pintype "passive"))
      (node (ref "C54") (pin "2") (pinfunction "2_2") (pintype "passive"))
      (node (ref "C55") (pin "2") (pinfunction "2_2") (pintype "passive"))
      (node (ref "R82") (pin "2") (pinfunction "2_2") (pintype "passive"))
      (node (ref "U17") (pin "21") (pinfunction "VREF+_21") (pintype "bidirectional"))
      (node (ref "U17") (pin "22") (pinfunction "VDDA_22") (pintype "power_in"))
    )
    (net (code "103") (name "unconnected-(P8-Reserved-Pad1)") (class "Default")
      (node (ref "P8") (pin "1") (pinfunction "Reserved_1") (pintype "passive+no_connect"))
    )
    (net (code "104") (name "unconnected-(P8-Reserved-Pad2)") (class "Default")
      (node (ref "P8") (pin "2") (pinfunction "Reserved_2") (pintype "passive+no_connect"))
    )
    (net (code "105") (name "unconnected-(U17A-PC4{slash}USART3_TX-Pad33)") (class "Default")
      (node (ref "U17") (pin "33") (pinfunction "PC4/USART3_TX_33") (pintype "bidirectional+no_connect"))
    )
  )
)
